# fab12_oscilloscope.net
KiCad netlist of a schematic drawn in EAGLE
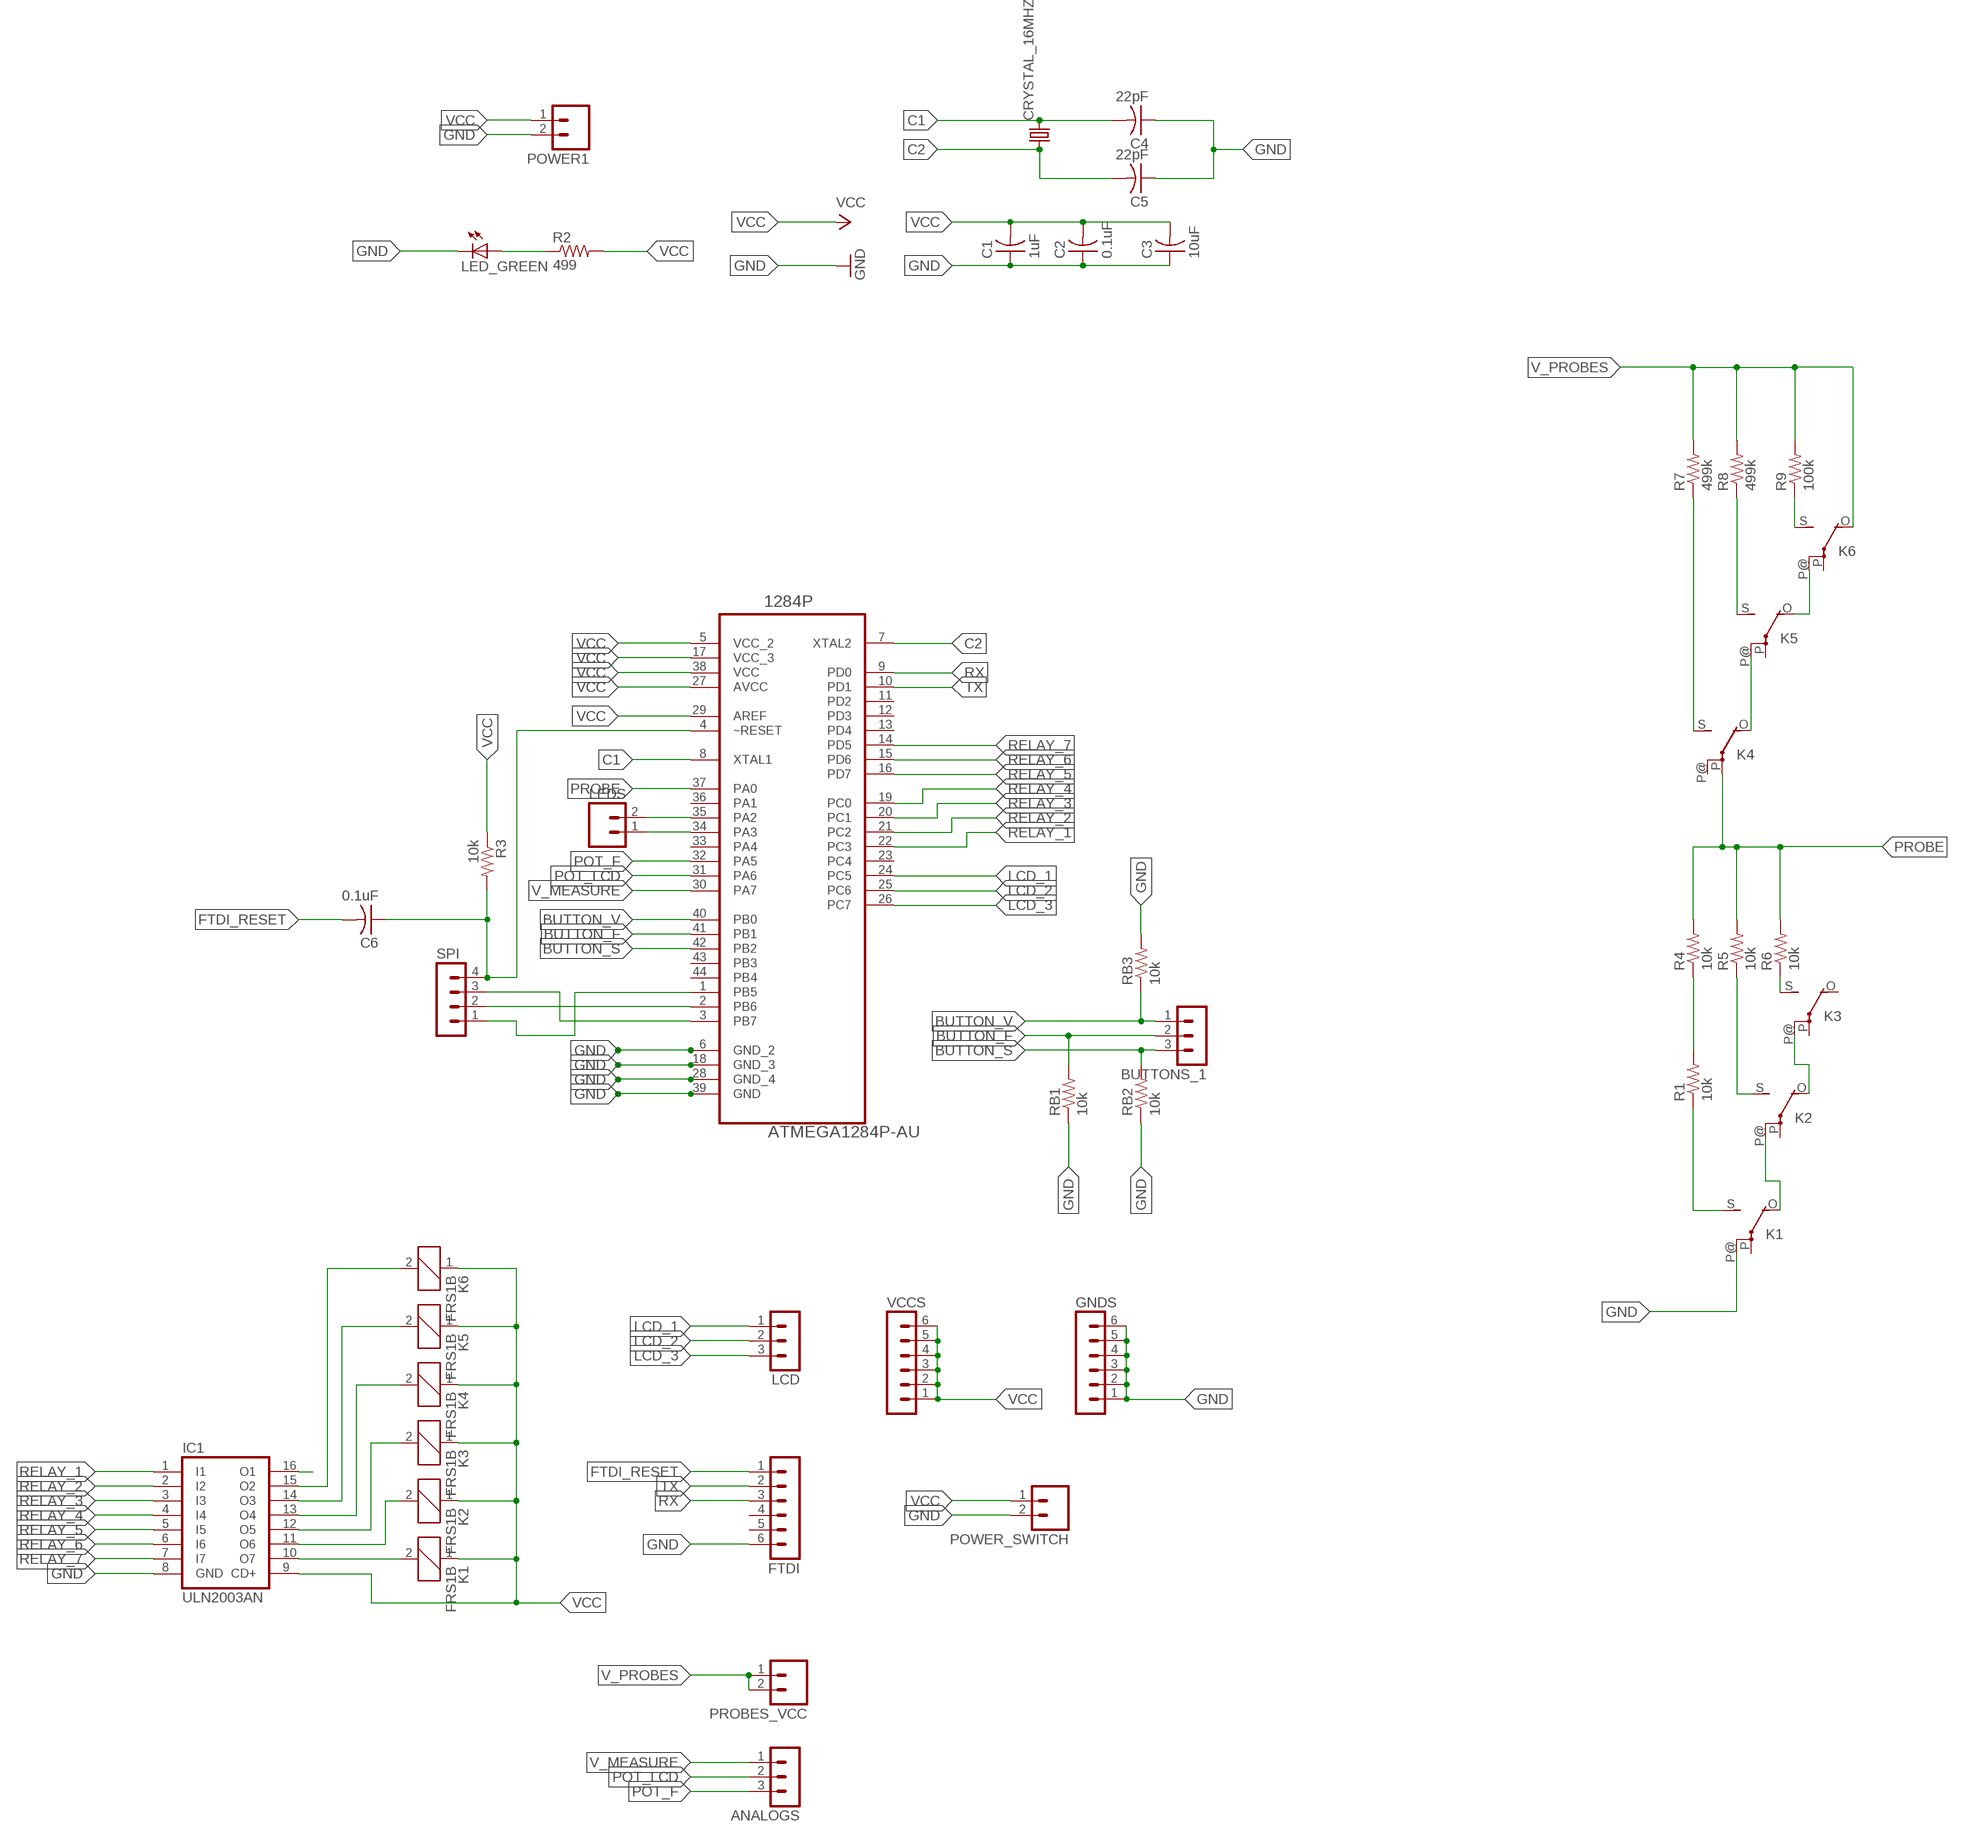
[diagram p0: schematic, sheet 1]

(export (version "E")
  (design (tool "Eeschema 10.0.6"))
  (components
    (comp (ref "1284P")
      (value "ATMEGA1284P-AU")
      (footprint "eagle-import:QFP80P1200X1200X120-44N")
      (libsource (lib "eagle-import") (part "ATMEGA1284P-AU"))
    )
    (comp (ref "ANALOGS")
      (value "MA03-1")
      (footprint "eagle-import:MA03-1")
      (libsource (lib "eagle-import") (part "MA03-1"))
    )
    (comp (ref "BUTTONS_1")
      (value "MA03-1")
      (footprint "eagle-import:MA03-1")
      (libsource (lib "eagle-import") (part "MA03-1"))
    )
    (comp (ref "C1")
      (value "1uF")
      (footprint "eagle-import:C1206")
      (libsource (lib "eagle-import") (part "CAP-US1206"))
    )
    (comp (ref "C2")
      (value "0.1uF")
      (footprint "eagle-import:C1206")
      (libsource (lib "eagle-import") (part "CAP-US1206"))
    )
    (comp (ref "C3")
      (value "10uF")
      (footprint "eagle-import:C1206")
      (libsource (lib "eagle-import") (part "CAP-US1206"))
    )
    (comp (ref "C4")
      (value "22pF")
      (footprint "eagle-import:C1206")
      (libsource (lib "eagle-import") (part "CAP-US1206"))
    )
    (comp (ref "C5")
      (value "22pF")
      (footprint "eagle-import:C1206")
      (libsource (lib "eagle-import") (part "CAP-US1206"))
    )
    (comp (ref "C6")
      (value "0.1uF")
      (footprint "eagle-import:C1206")
      (libsource (lib "eagle-import") (part "CAP-US1206"))
    )
    (comp (ref "CRYSTAL_16MHZ")
      (value "CRYSTALHC49UP")
      (footprint "eagle-import:HC49UP")
      (libsource (lib "eagle-import") (part "CRYSTALHC49UP"))
    )
    (comp (ref "FTDI")
      (value "MA06-1")
      (footprint "eagle-import:MA06-1")
      (libsource (lib "eagle-import") (part "MA06-1"))
    )
    (comp (ref "GNDS")
      (value "MA06-1")
      (footprint "eagle-import:MA06-1")
      (libsource (lib "eagle-import") (part "MA06-1"))
    )
    (comp (ref "IC1")
      (value "ULN2003AN")
      (footprint "eagle-import:DIL16")
      (libsource (lib "eagle-import") (part "ULN2003AN"))
    )
    (comp (ref "K1")
      (value "FRS1B")
      (footprint "eagle-import:FRS1B")
      (libsource (lib "eagle-import") (part "FRS1B"))
    )
    (comp (ref "K2")
      (value "FRS1B")
      (footprint "eagle-import:FRS1B")
      (libsource (lib "eagle-import") (part "FRS1B"))
    )
    (comp (ref "K3")
      (value "FRS1B")
      (footprint "eagle-import:FRS1B")
      (libsource (lib "eagle-import") (part "FRS1B"))
    )
    (comp (ref "K4")
      (value "FRS1B")
      (footprint "eagle-import:FRS1B")
      (libsource (lib "eagle-import") (part "FRS1B"))
    )
    (comp (ref "K5")
      (value "FRS1B")
      (footprint "eagle-import:FRS1B")
      (libsource (lib "eagle-import") (part "FRS1B"))
    )
    (comp (ref "K6")
      (value "FRS1B")
      (footprint "eagle-import:FRS1B")
      (libsource (lib "eagle-import") (part "FRS1B"))
    )
    (comp (ref "LCD")
      (value "MA03-1")
      (footprint "eagle-import:MA03-1")
      (libsource (lib "eagle-import") (part "MA03-1"))
    )
    (comp (ref "LEDS")
      (value "M02")
      (footprint "eagle-import:02P")
      (libsource (lib "eagle-import") (part "M02"))
    )
    (comp (ref "LED_GREEN")
      (value "LED1206")
      (footprint "eagle-import:1206")
      (libsource (lib "eagle-import") (part "LED1206"))
    )
    (comp (ref "POWER1")
      (value "M02")
      (footprint "eagle-import:02P")
      (libsource (lib "eagle-import") (part "M02"))
    )
    (comp (ref "POWER_SWITCH")
      (value "M02")
      (footprint "eagle-import:02P")
      (libsource (lib "eagle-import") (part "M02"))
    )
    (comp (ref "PROBES_VCC")
      (value "M02")
      (footprint "eagle-import:02P")
      (libsource (lib "eagle-import") (part "M02"))
    )
    (comp (ref "R1")
      (value "10k")
      (footprint "eagle-import:R1206")
      (libsource (lib "eagle-import") (part "RES-US1206"))
    )
    (comp (ref "R2")
      (value "499")
      (footprint "eagle-import:R1206")
      (libsource (lib "eagle-import") (part "RES-US1206"))
    )
    (comp (ref "R3")
      (value "10k")
      (footprint "eagle-import:R1206")
      (libsource (lib "eagle-import") (part "RES-US1206"))
    )
    (comp (ref "R4")
      (value "10k")
      (footprint "eagle-import:R1206")
      (libsource (lib "eagle-import") (part "RES-US1206"))
    )
    (comp (ref "R5")
      (value "10k")
      (footprint "eagle-import:R1206")
      (libsource (lib "eagle-import") (part "RES-US1206"))
    )
    (comp (ref "R6")
      (value "10k")
      (footprint "eagle-import:R1206")
      (libsource (lib "eagle-import") (part "RES-US1206"))
    )
    (comp (ref "R7")
      (value "499k")
      (footprint "eagle-import:R1206")
      (libsource (lib "eagle-import") (part "RES-US1206"))
    )
    (comp (ref "R8")
      (value "499k")
      (footprint "eagle-import:R1206")
      (libsource (lib "eagle-import") (part "RES-US1206"))
    )
    (comp (ref "R9")
      (value "100k")
      (footprint "eagle-import:R1206")
      (libsource (lib "eagle-import") (part "RES-US1206"))
    )
    (comp (ref "RB1")
      (value "10k")
      (footprint "eagle-import:R1206")
      (libsource (lib "eagle-import") (part "RES-US1206"))
    )
    (comp (ref "RB2")
      (value "10k")
      (footprint "eagle-import:R1206")
      (libsource (lib "eagle-import") (part "RES-US1206"))
    )
    (comp (ref "RB3")
      (value "10k")
      (footprint "eagle-import:R1206")
      (libsource (lib "eagle-import") (part "RES-US1206"))
    )
    (comp (ref "SPI")
      (value "MA04-1")
      (footprint "eagle-import:MA04-1")
      (libsource (lib "eagle-import") (part "MA04-1"))
    )
    (comp (ref "VCCS")
      (value "MA06-1")
      (footprint "eagle-import:MA06-1")
      (libsource (lib "eagle-import") (part "MA06-1"))
    )
  )
  (nets
    (net (code "1") (name "BUTTON_F") (class "Default")
      (node (ref "1284P") (pin "41") (pinfunction "PB1_41") (pintype "bidirectional"))
      (node (ref "BUTTONS_1") (pin "2") (pinfunction "2_2") (pintype "passive"))
      (node (ref "RB1") (pin "2") (pinfunction "2_2") (pintype "passive"))
    )
    (net (code "2") (name "BUTTON_S") (class "Default")
      (node (ref "1284P") (pin "42") (pinfunction "PB2_42") (pintype "bidirectional"))
      (node (ref "BUTTONS_1") (pin "3") (pinfunction "3_3") (pintype "passive"))
      (node (ref "RB2") (pin "2") (pinfunction "2_2") (pintype "passive"))
    )
    (net (code "3") (name "BUTTON_V") (class "Default")
      (node (ref "1284P") (pin "40") (pinfunction "PB0_40") (pintype "bidirectional"))
      (node (ref "BUTTONS_1") (pin "1") (pinfunction "1_1") (pintype "passive"))
      (node (ref "RB3") (pin "1") (pinfunction "1_1") (pintype "passive"))
    )
    (net (code "4") (name "C1") (class "Default")
      (node (ref "1284P") (pin "8") (pinfunction "XTAL1_8") (pintype "input"))
      (node (ref "C4") (pin "2") (pinfunction "2_2") (pintype "passive"))
      (node (ref "CRYSTAL_16MHZ") (pin "2") (pinfunction "2_2") (pintype "passive"))
    )
    (net (code "5") (name "C2") (class "Default")
      (node (ref "1284P") (pin "7") (pinfunction "XTAL2_7") (pintype "output"))
      (node (ref "C5") (pin "2") (pinfunction "2_2") (pintype "passive"))
      (node (ref "CRYSTAL_16MHZ") (pin "1") (pinfunction "1_1") (pintype "passive"))
    )
    (net (code "6") (name "FTDI_RESET") (class "Default")
      (node (ref "C6") (pin "2") (pinfunction "2_2") (pintype "passive"))
      (node (ref "FTDI") (pin "1") (pinfunction "1_1") (pintype "passive"))
    )
    (net (code "7") (name "GND") (class "Default")
      (node (ref "1284P") (pin "6") (pinfunction "GND_2_6") (pintype "passive"))
      (node (ref "C1") (pin "1") (pinfunction "1_1") (pintype "passive"))
      (node (ref "C2") (pin "1") (pinfunction "1_1") (pintype "passive"))
      (node (ref "C3") (pin "1") (pinfunction "1_1") (pintype "passive"))
      (node (ref "C4") (pin "1") (pinfunction "1_1") (pintype "passive"))
      (node (ref "C5") (pin "1") (pinfunction "1_1") (pintype "passive"))
      (node (ref "FTDI") (pin "6") (pinfunction "6_6") (pintype "passive"))
      (node (ref "GNDS") (pin "1") (pinfunction "1_1") (pintype "passive"))
      (node (ref "GNDS") (pin "2") (pinfunction "2_2") (pintype "passive"))
      (node (ref "GNDS") (pin "3") (pinfunction "3_3") (pintype "passive"))
      (node (ref "GNDS") (pin "4") (pinfunction "4_4") (pintype "passive"))
      (node (ref "GNDS") (pin "5") (pinfunction "5_5") (pintype "passive"))
      (node (ref "GNDS") (pin "6") (pinfunction "6_6") (pintype "passive"))
      (node (ref "IC1") (pin "8") (pinfunction "GND_8") (pintype "power_in"))
      (node (ref "K1") (pin "P@") (pinfunction "P_P@") (pintype "passive"))
      (node (ref "LED_GREEN") (pin "2") (pinfunction "C_2") (pintype "passive"))
      (node (ref "POWER1") (pin "2") (pinfunction "2_2") (pintype "passive"))
      (node (ref "POWER_SWITCH") (pin "2") (pinfunction "2_2") (pintype "passive"))
      (node (ref "RB1") (pin "1") (pinfunction "1_1") (pintype "passive"))
      (node (ref "RB2") (pin "1") (pinfunction "1_1") (pintype "passive"))
      (node (ref "RB3") (pin "2") (pinfunction "2_2") (pintype "passive"))
    )
    (net (code "8") (name "LCD_1") (class "Default")
      (node (ref "1284P") (pin "24") (pinfunction "PC5_24") (pintype "bidirectional"))
      (node (ref "LCD") (pin "1") (pinfunction "1_1") (pintype "passive"))
    )
    (net (code "9") (name "LCD_2") (class "Default")
      (node (ref "1284P") (pin "25") (pinfunction "PC6_25") (pintype "bidirectional"))
      (node (ref "LCD") (pin "2") (pinfunction "2_2") (pintype "passive"))
    )
    (net (code "10") (name "LCD_3") (class "Default")
      (node (ref "1284P") (pin "26") (pinfunction "PC7_26") (pintype "bidirectional"))
      (node (ref "LCD") (pin "3") (pinfunction "3_3") (pintype "passive"))
    )
    (net (code "11") (name "Net-(1284P-PA2)") (class "Default")
      (node (ref "1284P") (pin "35") (pinfunction "PA2_35") (pintype "bidirectional"))
      (node (ref "LEDS") (pin "2") (pinfunction "2_2") (pintype "passive"))
    )
    (net (code "12") (name "Net-(1284P-PA3)") (class "Default")
      (node (ref "1284P") (pin "34") (pinfunction "PA3_34") (pintype "bidirectional"))
      (node (ref "LEDS") (pin "1") (pinfunction "1_1") (pintype "passive"))
    )
    (net (code "13") (name "Net-(1284P-PB5)") (class "Default")
      (node (ref "1284P") (pin "1") (pinfunction "PB5_1") (pintype "bidirectional"))
      (node (ref "SPI") (pin "1") (pinfunction "1_1") (pintype "passive"))
    )
    (net (code "14") (name "Net-(1284P-PB6)") (class "Default")
      (node (ref "1284P") (pin "2") (pinfunction "PB6_2") (pintype "bidirectional"))
      (node (ref "SPI") (pin "2") (pinfunction "2_2") (pintype "passive"))
    )
    (net (code "15") (name "Net-(1284P-PB7)") (class "Default")
      (node (ref "1284P") (pin "3") (pinfunction "PB7_3") (pintype "bidirectional"))
      (node (ref "SPI") (pin "3") (pinfunction "3_3") (pintype "passive"))
    )
    (net (code "16") (name "Net-(1284P-~{RESET})") (class "Default")
      (node (ref "1284P") (pin "4") (pinfunction "~{RESET}_4") (pintype "input"))
      (node (ref "C6") (pin "1") (pinfunction "1_1") (pintype "passive"))
      (node (ref "R3") (pin "2") (pinfunction "2_2") (pintype "passive"))
      (node (ref "SPI") (pin "4") (pinfunction "4_4") (pintype "passive"))
    )
    (net (code "17") (name "Net-(IC1-O2)") (class "Default")
      (node (ref "IC1") (pin "15") (pinfunction "O2_15") (pintype "open_collector"))
      (node (ref "K6") (pin "2") (pinfunction "2_2") (pintype "passive"))
    )
    (net (code "18") (name "Net-(IC1-O3)") (class "Default")
      (node (ref "IC1") (pin "14") (pinfunction "O3_14") (pintype "open_collector"))
      (node (ref "K5") (pin "2") (pinfunction "2_2") (pintype "passive"))
    )
    (net (code "19") (name "Net-(IC1-O4)") (class "Default")
      (node (ref "IC1") (pin "13") (pinfunction "O4_13") (pintype "open_collector"))
      (node (ref "K4") (pin "2") (pinfunction "2_2") (pintype "passive"))
    )
    (net (code "20") (name "Net-(IC1-O5)") (class "Default")
      (node (ref "IC1") (pin "12") (pinfunction "O5_12") (pintype "open_collector"))
      (node (ref "K3") (pin "2") (pinfunction "2_2") (pintype "passive"))
    )
    (net (code "21") (name "Net-(IC1-O6)") (class "Default")
      (node (ref "IC1") (pin "11") (pinfunction "O6_11") (pintype "open_collector"))
      (node (ref "K2") (pin "2") (pinfunction "2_2") (pintype "passive"))
    )
    (net (code "22") (name "Net-(IC1-O7)") (class "Default")
      (node (ref "IC1") (pin "10") (pinfunction "O7_10") (pintype "open_collector"))
      (node (ref "K1") (pin "2") (pinfunction "2_2") (pintype "passive"))
    )
    (net (code "23") (name "Net-(K1-PadO)") (class "Default")
      (node (ref "K1") (pin "O") (pinfunction "O_O") (pintype "passive"))
      (node (ref "K2") (pin "P@") (pinfunction "P_P@") (pintype "passive"))
    )
    (net (code "24") (name "Net-(K1-PadS)") (class "Default")
      (node (ref "K1") (pin "S") (pinfunction "S_S") (pintype "passive"))
      (node (ref "R1") (pin "1") (pinfunction "1_1") (pintype "passive"))
    )
    (net (code "25") (name "Net-(K2-PadO)") (class "Default")
      (node (ref "K2") (pin "O") (pinfunction "O_O") (pintype "passive"))
      (node (ref "K3") (pin "P@") (pinfunction "P_P@") (pintype "passive"))
    )
    (net (code "26") (name "Net-(K2-PadS)") (class "Default")
      (node (ref "K2") (pin "S") (pinfunction "S_S") (pintype "passive"))
      (node (ref "R5") (pin "1") (pinfunction "1_1") (pintype "passive"))
    )
    (net (code "27") (name "Net-(K3-PadS)") (class "Default")
      (node (ref "K3") (pin "S") (pinfunction "S_S") (pintype "passive"))
      (node (ref "R6") (pin "1") (pinfunction "1_1") (pintype "passive"))
    )
    (net (code "28") (name "Net-(K4-PadO)") (class "Default")
      (node (ref "K4") (pin "O") (pinfunction "O_O") (pintype "passive"))
      (node (ref "K5") (pin "P@") (pinfunction "P_P@") (pintype "passive"))
    )
    (net (code "29") (name "Net-(K4-PadS)") (class "Default")
      (node (ref "K4") (pin "S") (pinfunction "S_S") (pintype "passive"))
      (node (ref "R7") (pin "1") (pinfunction "1_1") (pintype "passive"))
    )
    (net (code "30") (name "Net-(K5-PadO)") (class "Default")
      (node (ref "K5") (pin "O") (pinfunction "O_O") (pintype "passive"))
      (node (ref "K6") (pin "P@") (pinfunction "P_P@") (pintype "passive"))
    )
    (net (code "31") (name "Net-(K5-PadS)") (class "Default")
      (node (ref "K5") (pin "S") (pinfunction "S_S") (pintype "passive"))
      (node (ref "R8") (pin "1") (pinfunction "1_1") (pintype "passive"))
    )
    (net (code "32") (name "Net-(K6-PadS)") (class "Default")
      (node (ref "K6") (pin "S") (pinfunction "S_S") (pintype "passive"))
      (node (ref "R9") (pin "1") (pinfunction "1_1") (pintype "passive"))
    )
    (net (code "33") (name "Net-(LED_GREEN-A)") (class "Default")
      (node (ref "LED_GREEN") (pin "1") (pinfunction "A_1") (pintype "passive"))
      (node (ref "R2") (pin "1") (pinfunction "1_1") (pintype "passive"))
    )
    (net (code "34") (name "Net-(R1-Pad2)") (class "Default")
      (node (ref "R1") (pin "2") (pinfunction "2_2") (pintype "passive"))
      (node (ref "R4") (pin "1") (pinfunction "1_1") (pintype "passive"))
    )
    (net (code "35") (name "POT_F") (class "Default")
      (node (ref "1284P") (pin "32") (pinfunction "PA5_32") (pintype "bidirectional"))
      (node (ref "ANALOGS") (pin "3") (pinfunction "3_3") (pintype "passive"))
    )
    (net (code "36") (name "POT_LCD") (class "Default")
      (node (ref "1284P") (pin "31") (pinfunction "PA6_31") (pintype "bidirectional"))
      (node (ref "ANALOGS") (pin "2") (pinfunction "2_2") (pintype "passive"))
    )
    (net (code "37") (name "PROBE") (class "Default")
      (node (ref "1284P") (pin "37") (pinfunction "PA0_37") (pintype "bidirectional"))
      (node (ref "K4") (pin "P") (pinfunction "P_P") (pintype "passive"))
      (node (ref "R4") (pin "2") (pinfunction "2_2") (pintype "passive"))
      (node (ref "R5") (pin "2") (pinfunction "2_2") (pintype "passive"))
      (node (ref "R6") (pin "2") (pinfunction "2_2") (pintype "passive"))
    )
    (net (code "38") (name "RELAY_1") (class "Default")
      (node (ref "1284P") (pin "22") (pinfunction "PC3_22") (pintype "bidirectional"))
      (node (ref "IC1") (pin "1") (pinfunction "I1_1") (pintype "input"))
    )
    (net (code "39") (name "RELAY_2") (class "Default")
      (node (ref "1284P") (pin "21") (pinfunction "PC2_21") (pintype "bidirectional"))
      (node (ref "IC1") (pin "2") (pinfunction "I2_2") (pintype "input"))
    )
    (net (code "40") (name "RELAY_3") (class "Default")
      (node (ref "1284P") (pin "20") (pinfunction "PC1_20") (pintype "bidirectional"))
      (node (ref "IC1") (pin "3") (pinfunction "I3_3") (pintype "input"))
    )
    (net (code "41") (name "RELAY_4") (class "Default")
      (node (ref "1284P") (pin "19") (pinfunction "PC0_19") (pintype "bidirectional"))
      (node (ref "IC1") (pin "4") (pinfunction "I4_4") (pintype "input"))
    )
    (net (code "42") (name "RELAY_5") (class "Default")
      (node (ref "1284P") (pin "16") (pinfunction "PD7_16") (pintype "bidirectional"))
      (node (ref "IC1") (pin "5") (pinfunction "I5_5") (pintype "input"))
    )
    (net (code "43") (name "RELAY_6") (class "Default")
      (node (ref "1284P") (pin "15") (pinfunction "PD6_15") (pintype "bidirectional"))
      (node (ref "IC1") (pin "6") (pinfunction "I6_6") (pintype "input"))
    )
    (net (code "44") (name "RELAY_7") (class "Default")
      (node (ref "1284P") (pin "14") (pinfunction "PD5_14") (pintype "bidirectional"))
      (node (ref "IC1") (pin "7") (pinfunction "I7_7") (pintype "input"))
    )
    (net (code "45") (name "RX") (class "Default")
      (node (ref "1284P") (pin "9") (pinfunction "PD0_9") (pintype "bidirectional"))
      (node (ref "FTDI") (pin "3") (pinfunction "3_3") (pintype "passive"))
    )
    (net (code "46") (name "TX") (class "Default")
      (node (ref "1284P") (pin "10") (pinfunction "PD1_10") (pintype "bidirectional"))
      (node (ref "FTDI") (pin "2") (pinfunction "2_2") (pintype "passive"))
    )
    (net (code "47") (name "VCC") (class "Default")
      (node (ref "1284P") (pin "17") (pinfunction "VCC_3_17") (pintype "power_in"))
      (node (ref "1284P") (pin "27") (pinfunction "AVCC_27") (pintype "power_in"))
      (node (ref "1284P") (pin "29") (pinfunction "AREF_29") (pintype "input"))
      (node (ref "1284P") (pin "5") (pinfunction "VCC_2_5") (pintype "power_in"))
      (node (ref "C1") (pin "2") (pinfunction "2_2") (pintype "passive"))
      (node (ref "C2") (pin "2") (pinfunction "2_2") (pintype "passive"))
      (node (ref "C3") (pin "2") (pinfunction "2_2") (pintype "passive"))
      (node (ref "IC1") (pin "9") (pinfunction "CD+_9") (pintype "passive"))
      (node (ref "K1") (pin "1") (pinfunction "1_1") (pintype "passive"))
      (node (ref "K2") (pin "1") (pinfunction "1_1") (pintype "passive"))
      (node (ref "K3") (pin "1") (pinfunction "1_1") (pintype "passive"))
      (node (ref "K4") (pin "1") (pinfunction "1_1") (pintype "passive"))
      (node (ref "K5") (pin "1") (pinfunction "1_1") (pintype "passive"))
      (node (ref "K6") (pin "1") (pinfunction "1_1") (pintype "passive"))
      (node (ref "POWER1") (pin "1") (pinfunction "1_1") (pintype "passive"))
      (node (ref "POWER_SWITCH") (pin "1") (pinfunction "1_1") (pintype "passive"))
      (node (ref "R2") (pin "2") (pinfunction "2_2") (pintype "passive"))
      (node (ref "R3") (pin "1") (pinfunction "1_1") (pintype "passive"))
      (node (ref "VCCS") (pin "1") (pinfunction "1_1") (pintype "passive"))
      (node (ref "VCCS") (pin "2") (pinfunction "2_2") (pintype "passive"))
      (node (ref "VCCS") (pin "3") (pinfunction "3_3") (pintype "passive"))
      (node (ref "VCCS") (pin "4") (pinfunction "4_4") (pintype "passive"))
      (node (ref "VCCS") (pin "5") (pinfunction "5_5") (pintype "passive"))
      (node (ref "VCCS") (pin "6") (pinfunction "6_6") (pintype "passive"))
    )
    (net (code "48") (name "V_MEASURE") (class "Default")
      (node (ref "1284P") (pin "30") (pinfunction "PA7_30") (pintype "bidirectional"))
      (node (ref "ANALOGS") (pin "1") (pinfunction "1_1") (pintype "passive"))
    )
    (net (code "49") (name "V_PROBES") (class "Default")
      (node (ref "K6") (pin "O") (pinfunction "O_O") (pintype "passive"))
      (node (ref "PROBES_VCC") (pin "1") (pinfunction "1_1") (pintype "passive"))
      (node (ref "PROBES_VCC") (pin "2") (pinfunction "2_2") (pintype "passive"))
      (node (ref "R7") (pin "2") (pinfunction "2_2") (pintype "passive"))
      (node (ref "R8") (pin "2") (pinfunction "2_2") (pintype "passive"))
      (node (ref "R9") (pin "2") (pinfunction "2_2") (pintype "passive"))
    )
    (net (code "50") (name "unconnected-(1284P-GND-Pad39)") (class "Default")
      (node (ref "1284P") (pin "39") (pinfunction "GND_39") (pintype "passive"))
    )
    (net (code "51") (name "unconnected-(1284P-GND_3-Pad18)") (class "Default")
      (node (ref "1284P") (pin "18") (pinfunction "GND_3_18") (pintype "passive"))
    )
    (net (code "52") (name "unconnected-(1284P-GND_4-Pad28)") (class "Default")
      (node (ref "1284P") (pin "28") (pinfunction "GND_4_28") (pintype "passive"))
    )
    (net (code "53") (name "unconnected-(1284P-PA1-Pad36)") (class "Default")
      (node (ref "1284P") (pin "36") (pinfunction "PA1_36") (pintype "bidirectional"))
    )
    (net (code "54") (name "unconnected-(1284P-PA4-Pad33)") (class "Default")
      (node (ref "1284P") (pin "33") (pinfunction "PA4_33") (pintype "bidirectional"))
    )
    (net (code "55") (name "unconnected-(1284P-PB3-Pad43)") (class "Default")
      (node (ref "1284P") (pin "43") (pinfunction "PB3_43") (pintype "bidirectional"))
    )
    (net (code "56") (name "unconnected-(1284P-PB4-Pad44)") (class "Default")
      (node (ref "1284P") (pin "44") (pinfunction "PB4_44") (pintype "bidirectional"))
    )
    (net (code "57") (name "unconnected-(1284P-PC4-Pad23)") (class "Default")
      (node (ref "1284P") (pin "23") (pinfunction "PC4_23") (pintype "bidirectional"))
    )
    (net (code "58") (name "unconnected-(1284P-PD2-Pad11)") (class "Default")
      (node (ref "1284P") (pin "11") (pinfunction "PD2_11") (pintype "bidirectional"))
    )
    (net (code "59") (name "unconnected-(1284P-PD3-Pad12)") (class "Default")
      (node (ref "1284P") (pin "12") (pinfunction "PD3_12") (pintype "bidirectional"))
    )
    (net (code "60") (name "unconnected-(1284P-PD4-Pad13)") (class "Default")
      (node (ref "1284P") (pin "13") (pinfunction "PD4_13") (pintype "bidirectional"))
    )
    (net (code "61") (name "unconnected-(1284P-VCC-Pad38)") (class "Default")
      (node (ref "1284P") (pin "38") (pinfunction "VCC_38") (pintype "power_in"))
    )
    (net (code "62") (name "unconnected-(FTDI-Pad4)") (class "Default")
      (node (ref "FTDI") (pin "4") (pinfunction "4_4") (pintype "passive"))
    )
    (net (code "63") (name "unconnected-(FTDI-Pad5)") (class "Default")
      (node (ref "FTDI") (pin "5") (pinfunction "5_5") (pintype "passive"))
    )
    (net (code "64") (name "unconnected-(IC1-O1-Pad16)") (class "Default")
      (node (ref "IC1") (pin "16") (pinfunction "O1_16") (pintype "open_collector"))
    )
    (net (code "65") (name "unconnected-(K1-PadP)") (class "Default")
      (node (ref "K1") (pin "P") (pinfunction "P_P") (pintype "passive"))
    )
    (net (code "66") (name "unconnected-(K2-PadP)") (class "Default")
      (node (ref "K2") (pin "P") (pinfunction "P_P") (pintype "passive"))
    )
    (net (code "67") (name "unconnected-(K3-PadO)") (class "Default")
      (node (ref "K3") (pin "O") (pinfunction "O_O") (pintype "passive"))
    )
    (net (code "68") (name "unconnected-(K3-PadP)") (class "Default")
      (node (ref "K3") (pin "P") (pinfunction "P_P") (pintype "passive"))
    )
    (net (code "69") (name "unconnected-(K4B-P-PadP@)") (class "Default")
      (node (ref "K4") (pin "P@") (pinfunction "P_P@") (pintype "passive"))
    )
    (net (code "70") (name "unconnected-(K5-PadP)") (class "Default")
      (node (ref "K5") (pin "P") (pinfunction "P_P") (pintype "passive"))
    )
    (net (code "71") (name "unconnected-(K6-PadP)") (class "Default")
      (node (ref "K6") (pin "P") (pinfunction "P_P") (pintype "passive"))
    )
  )
)
